# TLM_002_MAX31856.net
KiCad netlist of a schematic drawn in Altium Designer
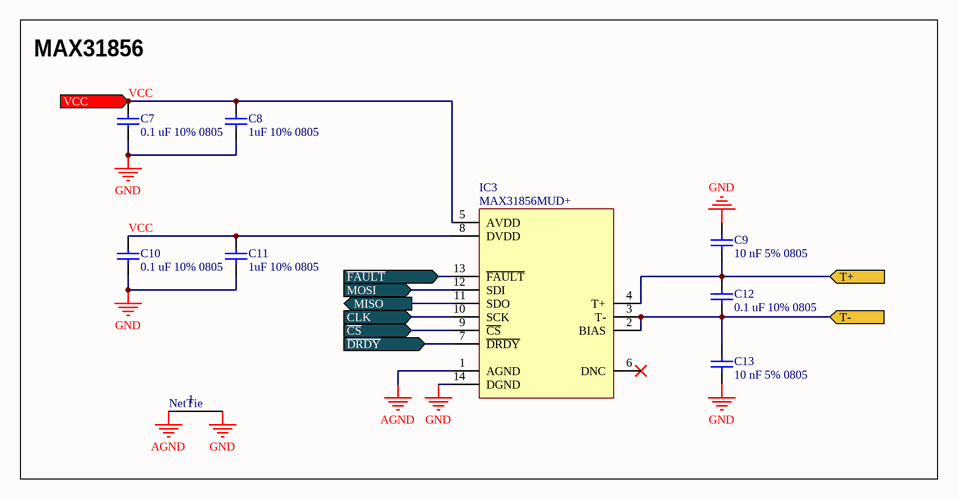
[diagram p0: TLM_002_MAX31856.SchDoc]

(export (version "E")
  (design (tool "Eeschema 10.0.6"))
  (components
    (comp (ref "1")
      (value "NetTie")
      (footprint "NetTie")
      (libsource (lib "Generic-Schematic-Library") (part "NetTie"))
    )
    (comp (ref "C7")
      (value "0.1 uF 10% 0805")
      (footprint "CAPC2013X140X50ML20T25")
      (fields
        (field (name "PART NUMBER") "0805DD104KAT2A")
        (field (name "MANUFACTURER") "AVX Interconnect / Elco")
      )
      (libsource (lib "Altium Content Vault") (part "CAP"))
    )
    (comp (ref "C8")
      (value "1uF 10% 0805")
      (footprint "CAPC2013X145X50NL20T20")
      (fields (field (name "PART NUMBER") "VJ0805Y105KXQRW1BC") (field (name "MANUFACTURER") "Vitramon"))
      (libsource (lib "Altium Content Vault") (part "CAP"))
    )
    (comp (ref "C9")
      (value "10 nF 5% 0805")
      (footprint "CAPC2013X94X50LL20T25")
      (fields
        (field (name "MANUFACTURER") "AVX Interconnect / Elco")
        (field (name "PART NUMBER") "08053C103JAT2A")
      )
      (libsource (lib "Altium Content Vault") (part "CAP"))
    )
    (comp (ref "C10")
      (value "0.1 uF 10% 0805")
      (footprint "CAPC2013X140X50ML20T25")
      (fields
        (field (name "PART NUMBER") "0805DD104KAT2A")
        (field (name "MANUFACTURER") "AVX Interconnect / Elco")
      )
      (libsource (lib "Altium Content Vault") (part "CAP"))
    )
    (comp (ref "C11")
      (value "1uF 10% 0805")
      (footprint "CAPC2013X145X50NL20T20")
      (fields (field (name "PART NUMBER") "VJ0805Y105KXQRW1BC") (field (name "MANUFACTURER") "Vitramon"))
      (libsource (lib "Altium Content Vault") (part "CAP"))
    )
    (comp (ref "C12")
      (value "0.1 uF 10% 0805")
      (footprint "CAPC2013X140X50ML20T25")
      (fields
        (field (name "PART NUMBER") "0805DD104KAT2A")
        (field (name "MANUFACTURER") "AVX Interconnect / Elco")
      )
      (libsource (lib "Altium Content Vault") (part "CAP"))
    )
    (comp (ref "C13")
      (value "10 nF 5% 0805")
      (footprint "CAPC2013X94X50LL20T25")
      (fields
        (field (name "MANUFACTURER") "AVX Interconnect / Elco")
        (field (name "PART NUMBER") "08053C103JAT2A")
      )
      (libsource (lib "Altium Content Vault") (part "CAP"))
    )
    (comp (ref "IC3")
      (value "MAX31856MUD+")
      (footprint "SamacSys:SOP65P640X110-14N")
      (description "Integrated Circuit")
      (fields (field (name "MOUSER PART NUMBER") "700-MAX31856MUD+"))
      (libsource (lib "SamacSys") (part "MAX31856MUD+"))
    )
  )
  (nets
    (net (code "1") (name "/CLK") (class "Default")
      (node (ref "IC3") (pin "10") (pinfunction "SCK_10") (pintype "passive"))
    )
    (net (code "2") (name "/MISO") (class "Default")
      (node (ref "IC3") (pin "11") (pinfunction "SDO_11") (pintype "passive"))
    )
    (net (code "3") (name "/MOSI") (class "Default")
      (node (ref "IC3") (pin "12") (pinfunction "SDI_12") (pintype "passive"))
    )
    (net (code "4") (name "/T+") (class "Default")
      (node (ref "C12") (pin "2") (pinfunction "2_2") (pintype "passive"))
      (node (ref "C9") (pin "1") (pinfunction "1_1") (pintype "passive"))
      (node (ref "IC3") (pin "4") (pinfunction "T+_4") (pintype "passive"))
    )
    (net (code "5") (name "/T-") (class "Default")
      (node (ref "C12") (pin "1") (pinfunction "1_1") (pintype "passive"))
      (node (ref "C13") (pin "2") (pinfunction "2_2") (pintype "passive"))
      (node (ref "IC3") (pin "2") (pinfunction "BIAS_2") (pintype "passive"))
      (node (ref "IC3") (pin "3") (pinfunction "T-_3") (pintype "passive"))
    )
    (net (code "6") (name "/VCC") (class "Default")
      (node (ref "C10") (pin "2") (pinfunction "2_2") (pintype "passive"))
      (node (ref "C11") (pin "2") (pinfunction "2_2") (pintype "passive"))
      (node (ref "C7") (pin "2") (pinfunction "2_2") (pintype "passive"))
      (node (ref "C8") (pin "2") (pinfunction "2_2") (pintype "passive"))
      (node (ref "IC3") (pin "5") (pinfunction "AVDD_5") (pintype "passive"))
      (node (ref "IC3") (pin "8") (pinfunction "DVDD_8") (pintype "passive"))
    )
    (net (code "7") (name "/~{CS}") (class "Default")
      (node (ref "IC3") (pin "9") (pinfunction "~{CS}_9") (pintype "passive"))
    )
    (net (code "8") (name "/~{DRDY}") (class "Default")
      (node (ref "IC3") (pin "7") (pinfunction "~{DRDY}_7") (pintype "passive"))
    )
    (net (code "9") (name "/~{FAULT}") (class "Default")
      (node (ref "IC3") (pin "13") (pinfunction "~{FAULT}_13") (pintype "passive"))
    )
    (net (code "10") (name "AGND") (class "Default")
      (node (ref "1") (pin "1") (pinfunction "1_1") (pintype "passive"))
      (node (ref "IC3") (pin "1") (pinfunction "AGND_1") (pintype "passive"))
    )
    (net (code "11") (name "GND") (class "Default")
      (node (ref "1") (pin "2") (pinfunction "2_2") (pintype "passive"))
      (node (ref "C10") (pin "1") (pinfunction "1_1") (pintype "passive"))
      (node (ref "C11") (pin "1") (pinfunction "1_1") (pintype "passive"))
      (node (ref "C13") (pin "1") (pinfunction "1_1") (pintype "passive"))
      (node (ref "C7") (pin "1") (pinfunction "1_1") (pintype "passive"))
      (node (ref "C8") (pin "1") (pinfunction "1_1") (pintype "passive"))
      (node (ref "C9") (pin "2") (pinfunction "2_2") (pintype "passive"))
      (node (ref "IC3") (pin "14") (pinfunction "DGND_14") (pintype "passive"))
    )
    (net (code "12") (name "unconnected-(IC3-DNC-Pad6)") (class "Default")
      (node (ref "IC3") (pin "6") (pinfunction "DNC_6") (pintype "passive+no_connect"))
    )
  )
)
